# ESP32_Albums.net
KiCad netlist of a schematic drawn in Altium Designer
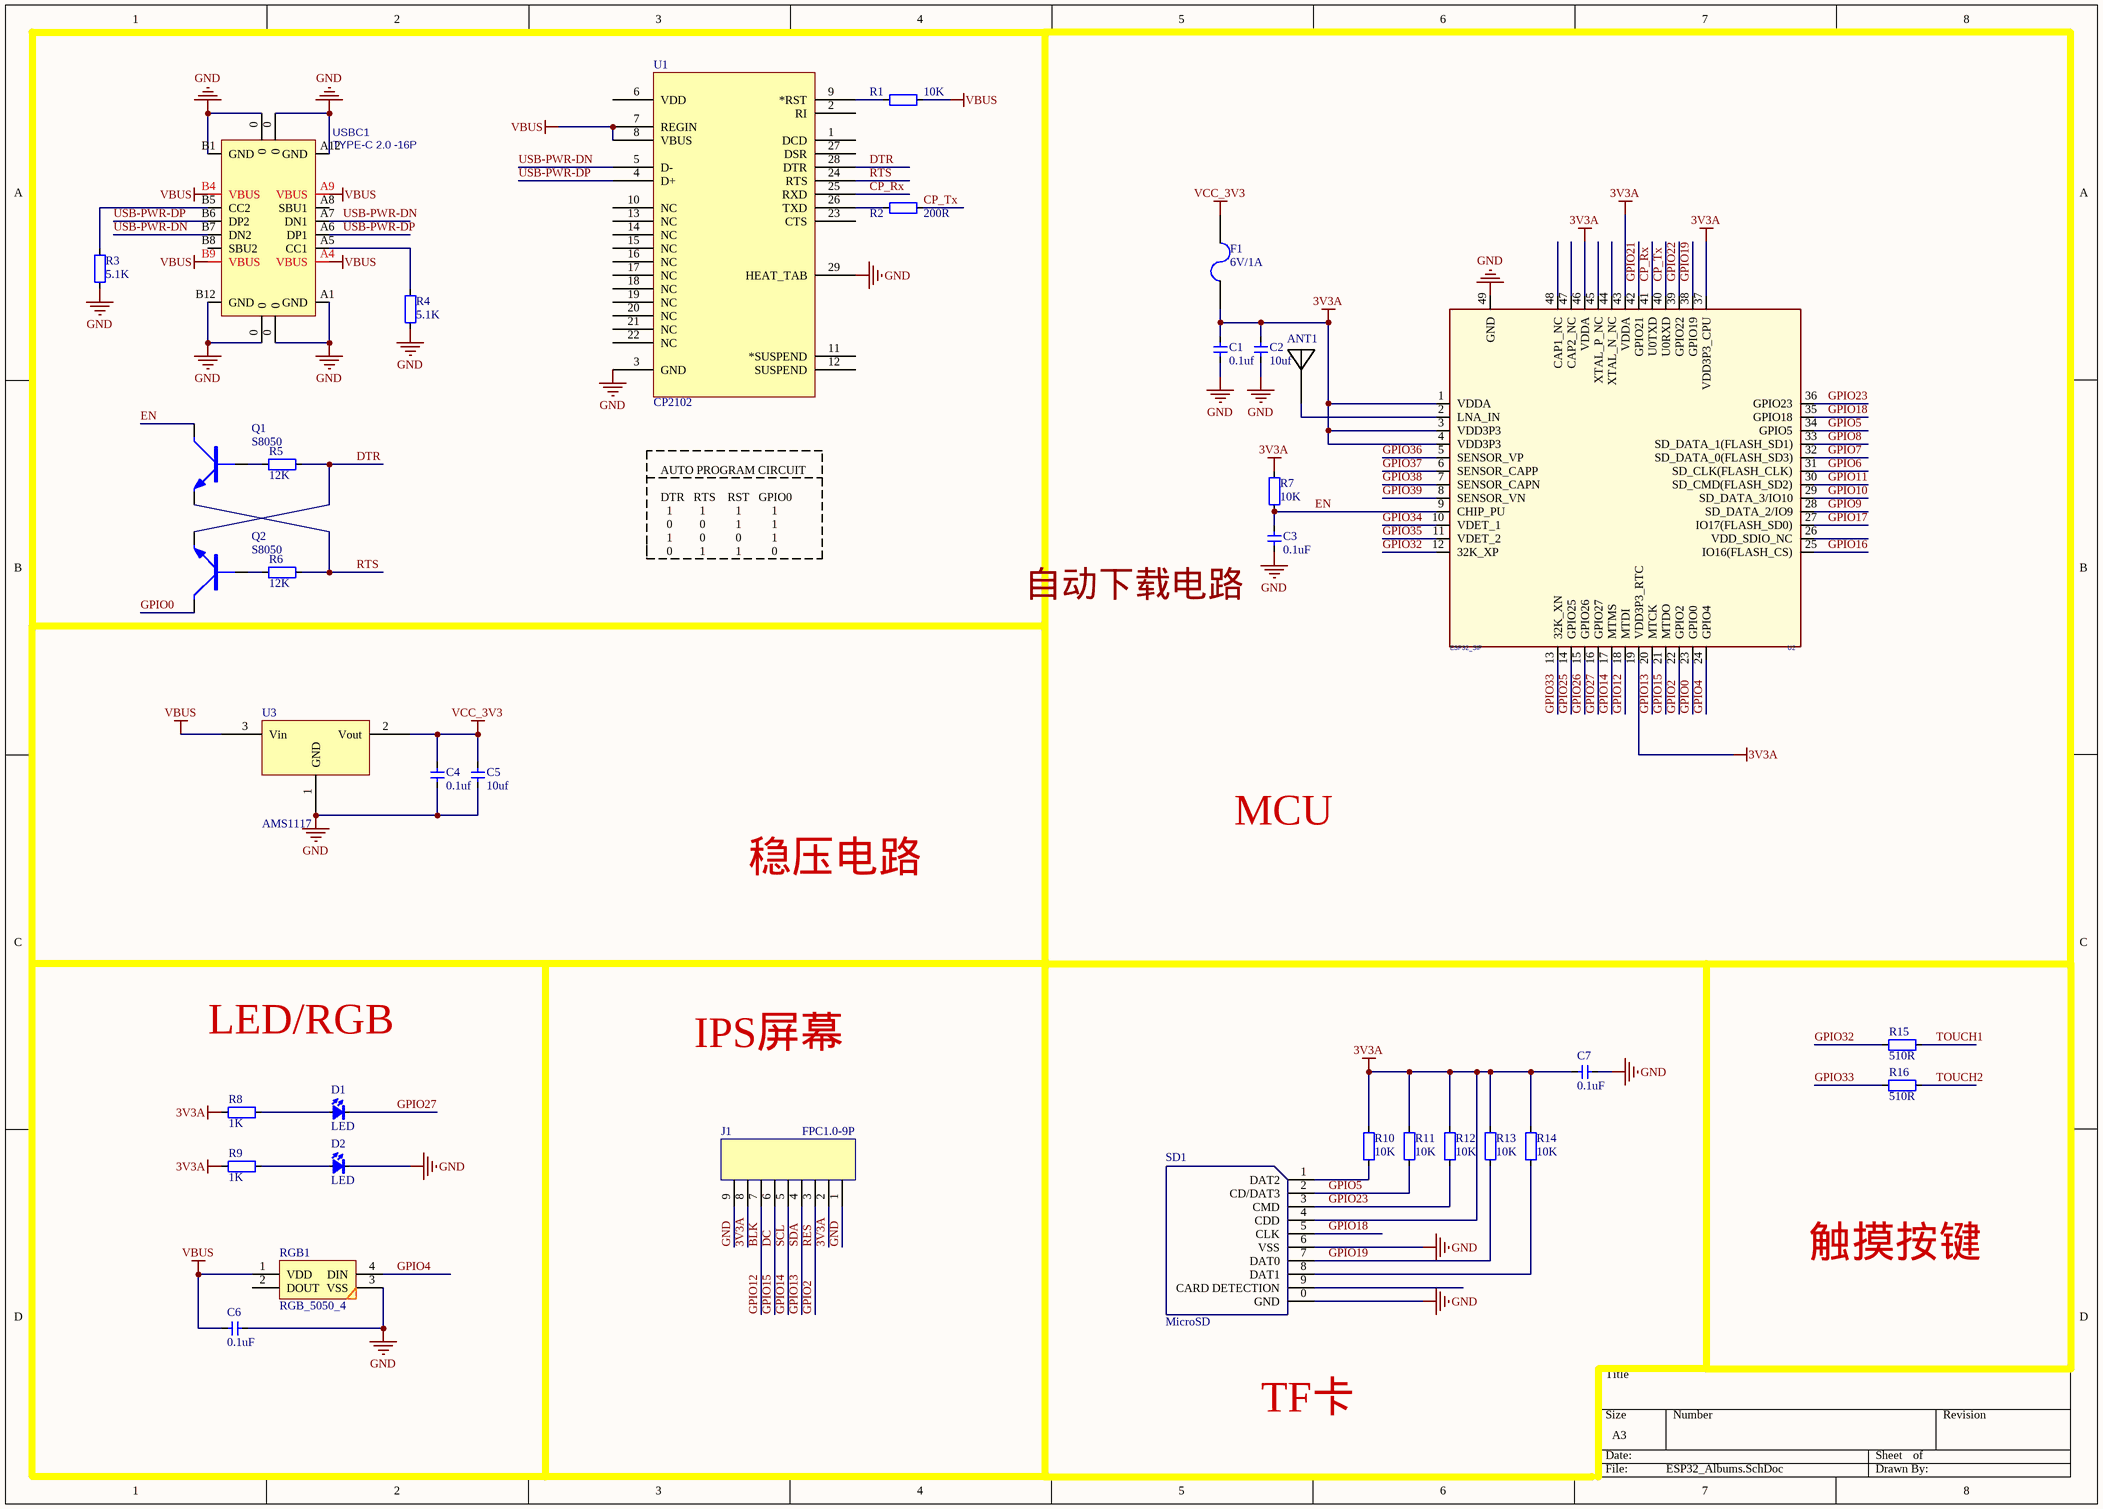
[diagram p0: ESP32_Albums.SchDoc]

(export (version "E")
  (design (tool "Eeschema 10.0.6"))
  (components
    (comp (ref "ANT1")
      (value "ANT2")
      (footprint "ANT2051")
      (description "贴片天线")
      (libsource (lib "射频天线") (part "ANT2"))
    )
    (comp (ref "C1")
      (value "0.1uf")
      (footprint "0603C")
      (description "无极性电容")
      (libsource (lib "电容") (part "CAP"))
    )
    (comp (ref "C2")
      (value "10uf")
      (footprint "0603C")
      (description "无极性电容")
      (libsource (lib "电容") (part "CAP"))
    )
    (comp (ref "C3")
      (value "0.1uF")
      (footprint "0603C")
      (description "无极性电容")
      (libsource (lib "电容") (part "CAP"))
    )
    (comp (ref "C4")
      (value "0.1uf")
      (footprint "0603C")
      (description "无极性电容")
      (libsource (lib "电容") (part "CAP"))
    )
    (comp (ref "C5")
      (value "10uf")
      (footprint "0603C")
      (description "无极性电容")
      (libsource (lib "电容") (part "CAP"))
    )
    (comp (ref "C6")
      (value "0.1uF")
      (footprint "0603C")
      (description "无极性电容")
      (libsource (lib "电容") (part "CAP"))
    )
    (comp (ref "C7")
      (value "0.1uF")
      (footprint "0603C")
      (description "无极性电容")
      (libsource (lib "电容") (part "CAP"))
    )
    (comp (ref "D1") (value "LED") (footprint "LED_0603_R") (libsource (lib "LED") (part "LED")))
    (comp (ref "D2") (value "LED") (footprint "LED_0603_R") (libsource (lib "LED") (part "LED")))
    (comp (ref "F1") (value "6V/1A") (footprint "FUSE-0805") (libsource (lib "保险丝") (part "FUSE")))
    (comp (ref "J1")
      (value "FPC1.0-9P")
      (footprint "FPC1.0-9P")
      (description "贴片")
      (libsource (lib "FPC") (part "FPC1.0-9P"))
    )
    (comp (ref "Q1")
      (value "S8050")
      (footprint "SOT-23")
      (description "NPN三极管")
      (libsource (lib "三极管") (part "NPN"))
    )
    (comp (ref "Q2")
      (value "S8050")
      (footprint "SOT-23")
      (description "NPN三极管")
      (libsource (lib "三极管") (part "NPN"))
    )
    (comp (ref "R1") (value "10K") (footprint "0603R") (libsource (lib "") (part "RES_1")))
    (comp (ref "R2") (value "200R") (footprint "0603R") (libsource (lib "") (part "RES_1")))
    (comp (ref "R3") (value "5.1K") (footprint "0603R") (libsource (lib "电阻") (part "RES")))
    (comp (ref "R4") (value "5.1K") (footprint "0603R") (libsource (lib "电阻") (part "RES")))
    (comp (ref "R5") (value "12K") (footprint "0603R") (libsource (lib "") (part "RES_1")))
    (comp (ref "R6") (value "12K") (footprint "0603R") (libsource (lib "") (part "RES_1")))
    (comp (ref "R7") (value "10K") (footprint "0603R") (libsource (lib "电阻") (part "RES")))
    (comp (ref "R8") (value "1K") (footprint "0603R") (libsource (lib "") (part "RES_1")))
    (comp (ref "R9") (value "1K") (footprint "0603R") (libsource (lib "") (part "RES_1")))
    (comp (ref "R10") (value "10K") (footprint "0603R") (libsource (lib "电阻") (part "RES")))
    (comp (ref "R11") (value "10K") (footprint "0603R") (libsource (lib "电阻") (part "RES")))
    (comp (ref "R12") (value "10K") (footprint "0603R") (libsource (lib "电阻") (part "RES")))
    (comp (ref "R13") (value "10K") (footprint "0603R") (libsource (lib "电阻") (part "RES")))
    (comp (ref "R14") (value "10K") (footprint "0603R") (libsource (lib "电阻") (part "RES")))
    (comp (ref "R15") (value "510R") (footprint "0603R") (libsource (lib "") (part "RES_1")))
    (comp (ref "R16") (value "510R") (footprint "0603R") (libsource (lib "") (part "RES_1")))
    (comp (ref "RGB1")
      (value "RGB_5050_4")
      (footprint "RGB_5050_4")
      (libsource (lib "LED") (part "RGB_5050_4"))
    )
    (comp (ref "SD1") (value "MicroSD") (footprint "Micro SD") (libsource (lib "SD Card") (part "MicroSD")))
    (comp (ref "U1")
      (value "CP2102")
      (footprint "LC-QFN-28_5x5x05P")
      (description "USB转TTL")
      (libsource (lib "通讯系列IC") (part "CP2102"))
    )
    (comp (ref "U2")
      (value "ESP32_SIP")
      (footprint "QFN-48_7X7")
      (libsource (lib "ESP32系列") (part "ESP32-PICO"))
    )
    (comp (ref "U3")
      (value "AMS1117")
      (footprint "SOT223")
      (description "三端稳压芯片")
      (libsource (lib "电源芯片") (part "AMS1117"))
    )
    (comp (ref "USBC1")
      (value "TYPE-C 2.0 -16P")
      (footprint "USB-C-SMD_16P")
      (description "USB2.0 Type-C 16Pin  母座")
      (libsource (lib "USB") (part "USB2.0_Type-C_16Pin"))
    )
  )
  (nets
    (net (code "1") (name "/BLK") (class "Default")
      (node (ref "J1") (pin "7") (pinfunction "7_7") (pintype "passive"))
      (node (ref "U2") (pin "18") (pinfunction "MTDI_18") (pintype "passive"))
    )
    (net (code "2") (name "/CP_Rx") (class "Default")
      (node (ref "U1") (pin "25") (pinfunction "RXD_25") (pintype "passive"))
      (node (ref "U2") (pin "41") (pinfunction "U0TXD_41") (pintype "power_in"))
    )
    (net (code "3") (name "/CP_Tx") (class "Default")
      (node (ref "R2") (pin "2") (pinfunction "2_2") (pintype "passive"))
      (node (ref "U2") (pin "40") (pinfunction "U0RXD_40") (pintype "power_in"))
    )
    (net (code "4") (name "/DC") (class "Default")
      (node (ref "J1") (pin "6") (pinfunction "6_6") (pintype "passive"))
      (node (ref "U2") (pin "21") (pinfunction "MTDO_21") (pintype "passive"))
    )
    (net (code "5") (name "/DTR") (class "Default")
      (node (ref "Q2") (pin "E") (pinfunction "E_E") (pintype "passive"))
      (node (ref "R5") (pin "2") (pinfunction "2_2") (pintype "passive"))
      (node (ref "U1") (pin "28") (pinfunction "DTR_28") (pintype "passive"))
    )
    (net (code "6") (name "/EN") (class "Default")
      (node (ref "C3") (pin "2") (pinfunction "2_2") (pintype "passive"))
      (node (ref "Q1") (pin "C") (pinfunction "C_C") (pintype "passive"))
      (node (ref "R7") (pin "1") (pinfunction "1_1") (pintype "passive"))
      (node (ref "U2") (pin "9") (pinfunction "CHIP_PU_9") (pintype "passive"))
    )
    (net (code "7") (name "/GPIO0") (class "Default")
      (node (ref "Q2") (pin "C") (pinfunction "C_C") (pintype "passive"))
      (node (ref "U2") (pin "23") (pinfunction "GPIO0_23") (pintype "passive"))
    )
    (net (code "8") (name "/GPIO2") (class "Default")
      (node (ref "J1") (pin "3") (pinfunction "3_3") (pintype "passive"))
      (node (ref "U2") (pin "22") (pinfunction "GPIO2_22") (pintype "passive"))
    )
    (net (code "9") (name "/GPIO4") (class "Default")
      (node (ref "RGB1") (pin "4") (pinfunction "DIN_4") (pintype "passive"))
      (node (ref "U2") (pin "24") (pinfunction "GPIO4_24") (pintype "passive"))
    )
    (net (code "10") (name "/GPIO5") (class "Default")
      (node (ref "R11") (pin "1") (pinfunction "1_1") (pintype "passive"))
      (node (ref "SD1") (pin "2") (pinfunction "CD/DAT3_2") (pintype "passive"))
      (node (ref "U2") (pin "34") (pinfunction "GPIO5_34") (pintype "passive"))
    )
    (net (code "11") (name "/GPIO6") (class "Default")
      (node (ref "U2") (pin "31") (pinfunction "SD_CLK(FLASH_CLK)_31") (pintype "passive"))
    )
    (net (code "12") (name "/GPIO7") (class "Default")
      (node (ref "U2") (pin "32") (pinfunction "SD_DATA_0(FLASH_SD3)_32") (pintype "passive"))
    )
    (net (code "13") (name "/GPIO8") (class "Default")
      (node (ref "U2") (pin "33") (pinfunction "SD_DATA_1(FLASH_SD1)_33") (pintype "passive"))
    )
    (net (code "14") (name "/GPIO9") (class "Default")
      (node (ref "U2") (pin "28") (pinfunction "SD_DATA_2/IO9_28") (pintype "passive"))
    )
    (net (code "15") (name "/GPIO10") (class "Default")
      (node (ref "U2") (pin "29") (pinfunction "SD_DATA_3/IO10_29") (pintype "passive"))
    )
    (net (code "16") (name "/GPIO11") (class "Default")
      (node (ref "U2") (pin "30") (pinfunction "SD_CMD(FLASH_SD2)_30") (pintype "passive"))
    )
    (net (code "17") (name "/GPIO13") (class "Default")
      (node (ref "J1") (pin "4") (pinfunction "4_4") (pintype "passive"))
      (node (ref "U2") (pin "20") (pinfunction "MTCK_20") (pintype "passive"))
    )
    (net (code "18") (name "/GPIO14") (class "Default")
      (node (ref "J1") (pin "5") (pinfunction "5_5") (pintype "passive"))
      (node (ref "U2") (pin "17") (pinfunction "MTMS_17") (pintype "passive"))
    )
    (net (code "19") (name "/GPIO16") (class "Default")
      (node (ref "U2") (pin "25") (pinfunction "IO16(FLASH_CS)_25") (pintype "passive"))
    )
    (net (code "20") (name "/GPIO17") (class "Default")
      (node (ref "U2") (pin "27") (pinfunction "IO17(FLASH_SD0)_27") (pintype "passive"))
    )
    (net (code "21") (name "/GPIO18") (class "Default")
      (node (ref "SD1") (pin "5") (pinfunction "CLK_5") (pintype "passive"))
      (node (ref "U2") (pin "35") (pinfunction "GPIO18_35") (pintype "passive"))
    )
    (net (code "22") (name "/GPIO19") (class "Default")
      (node (ref "R13") (pin "1") (pinfunction "1_1") (pintype "passive"))
      (node (ref "SD1") (pin "7") (pinfunction "DAT0_7") (pintype "passive"))
      (node (ref "U2") (pin "38") (pinfunction "GPIO19_38") (pintype "passive"))
    )
    (net (code "23") (name "/GPIO21") (class "Default")
      (node (ref "U2") (pin "42") (pinfunction "GPIO21_42") (pintype "passive"))
    )
    (net (code "24") (name "/GPIO22") (class "Default")
      (node (ref "U2") (pin "39") (pinfunction "GPIO22_39") (pintype "passive"))
    )
    (net (code "25") (name "/GPIO23") (class "Default")
      (node (ref "R12") (pin "1") (pinfunction "1_1") (pintype "passive"))
      (node (ref "SD1") (pin "3") (pinfunction "CMD_3") (pintype "passive"))
      (node (ref "U2") (pin "36") (pinfunction "GPIO23_36") (pintype "passive"))
    )
    (net (code "26") (name "/GPIO25") (class "Default")
      (node (ref "U2") (pin "14") (pinfunction "GPIO25_14") (pintype "passive"))
    )
    (net (code "27") (name "/GPIO26") (class "Default")
      (node (ref "U2") (pin "15") (pinfunction "GPIO26_15") (pintype "passive"))
    )
    (net (code "28") (name "/GPIO27") (class "Default")
      (node (ref "D1") (pin "1") (pinfunction "A_1") (pintype "passive"))
      (node (ref "U2") (pin "16") (pinfunction "GPIO27_16") (pintype "passive"))
    )
    (net (code "29") (name "/GPIO32") (class "Default")
      (node (ref "R15") (pin "1") (pinfunction "1_1") (pintype "passive"))
      (node (ref "U2") (pin "12") (pinfunction "32K_XP_12") (pintype "passive"))
    )
    (net (code "30") (name "/GPIO33") (class "Default")
      (node (ref "R16") (pin "1") (pinfunction "1_1") (pintype "passive"))
      (node (ref "U2") (pin "13") (pinfunction "32K_XN_13") (pintype "passive"))
    )
    (net (code "31") (name "/GPIO34") (class "Default")
      (node (ref "U2") (pin "10") (pinfunction "VDET_1_10") (pintype "passive"))
    )
    (net (code "32") (name "/GPIO35") (class "Default")
      (node (ref "U2") (pin "11") (pinfunction "VDET_2_11") (pintype "passive"))
    )
    (net (code "33") (name "/GPIO36") (class "Default")
      (node (ref "U2") (pin "5") (pinfunction "SENSOR_VP_5") (pintype "passive"))
    )
    (net (code "34") (name "/GPIO37") (class "Default")
      (node (ref "U2") (pin "6") (pinfunction "SENSOR_CAPP_6") (pintype "passive"))
    )
    (net (code "35") (name "/GPIO38") (class "Default")
      (node (ref "U2") (pin "7") (pinfunction "SENSOR_CAPN_7") (pintype "passive"))
    )
    (net (code "36") (name "/GPIO39") (class "Default")
      (node (ref "U2") (pin "8") (pinfunction "SENSOR_VN_8") (pintype "passive"))
    )
    (net (code "37") (name "/RTS") (class "Default")
      (node (ref "Q1") (pin "E") (pinfunction "E_E") (pintype "passive"))
      (node (ref "R6") (pin "2") (pinfunction "2_2") (pintype "passive"))
      (node (ref "U1") (pin "24") (pinfunction "RTS_24") (pintype "passive"))
    )
    (net (code "38") (name "/TOUCH1") (class "Default")
      (node (ref "R15") (pin "2") (pinfunction "2_2") (pintype "passive"))
    )
    (net (code "39") (name "/TOUCH2") (class "Default")
      (node (ref "R16") (pin "2") (pinfunction "2_2") (pintype "passive"))
    )
    (net (code "40") (name "/USB-PWR-DN") (class "Default")
      (node (ref "U1") (pin "5") (pinfunction "D-_5") (pintype "passive"))
      (node (ref "USBC1") (pin "A7") (pinfunction "DN1_A7") (pintype "passive"))
      (node (ref "USBC1") (pin "B7") (pinfunction "DN2_B7") (pintype "passive"))
    )
    (net (code "41") (name "/USB-PWR-DP") (class "Default")
      (node (ref "U1") (pin "4") (pinfunction "D+_4") (pintype "passive"))
      (node (ref "USBC1") (pin "A6") (pinfunction "DP1_A6") (pintype "passive"))
      (node (ref "USBC1") (pin "B6") (pinfunction "DP2_B6") (pintype "passive"))
    )
    (net (code "42") (name "3V3A") (class "Default")
      (node (ref "C1") (pin "2") (pinfunction "2_2") (pintype "passive"))
      (node (ref "C2") (pin "2") (pinfunction "2_2") (pintype "passive"))
      (node (ref "C7") (pin "1") (pinfunction "1_1") (pintype "passive"))
      (node (ref "F1") (pin "1") (pinfunction "1_1") (pintype "passive"))
      (node (ref "J1") (pin "2") (pinfunction "2_2") (pintype "passive"))
      (node (ref "J1") (pin "8") (pinfunction "8_8") (pintype "passive"))
      (node (ref "R10") (pin "2") (pinfunction "2_2") (pintype "passive"))
      (node (ref "R11") (pin "2") (pinfunction "2_2") (pintype "passive"))
      (node (ref "R12") (pin "2") (pinfunction "2_2") (pintype "passive"))
      (node (ref "R13") (pin "2") (pinfunction "2_2") (pintype "passive"))
      (node (ref "R14") (pin "2") (pinfunction "2_2") (pintype "passive"))
      (node (ref "R7") (pin "2") (pinfunction "2_2") (pintype "passive"))
      (node (ref "R8") (pin "1") (pinfunction "1_1") (pintype "passive"))
      (node (ref "R9") (pin "1") (pinfunction "1_1") (pintype "passive"))
      (node (ref "SD1") (pin "4") (pinfunction "CDD_4") (pintype "passive"))
      (node (ref "U2") (pin "1") (pinfunction "VDDA_1") (pintype "power_in"))
      (node (ref "U2") (pin "19") (pinfunction "VDD3P3_RTC_19") (pintype "power_in"))
      (node (ref "U2") (pin "3") (pinfunction "VDD3P3_3") (pintype "power_in"))
      (node (ref "U2") (pin "37") (pinfunction "VDD3P3_CPU_37") (pintype "power_in"))
      (node (ref "U2") (pin "4") (pinfunction "VDD3P3_4") (pintype "power_in"))
      (node (ref "U2") (pin "43") (pinfunction "VDDA_43") (pintype "power_in"))
      (node (ref "U2") (pin "46") (pinfunction "VDDA_46") (pintype "power_in"))
    )
    (net (code "43") (name "GND") (class "Default")
      (node (ref "C1") (pin "1") (pinfunction "1_1") (pintype "passive"))
      (node (ref "C2") (pin "1") (pinfunction "1_1") (pintype "passive"))
      (node (ref "C3") (pin "1") (pinfunction "1_1") (pintype "passive"))
      (node (ref "C4") (pin "1") (pinfunction "1_1") (pintype "passive"))
      (node (ref "C5") (pin "1") (pinfunction "1_1") (pintype "passive"))
      (node (ref "C6") (pin "2") (pinfunction "2_2") (pintype "passive"))
      (node (ref "C7") (pin "2") (pinfunction "2_2") (pintype "passive"))
      (node (ref "D2") (pin "1") (pinfunction "A_1") (pintype "passive"))
      (node (ref "J1") (pin "1") (pinfunction "1_1") (pintype "passive"))
      (node (ref "J1") (pin "9") (pinfunction "9_9") (pintype "passive"))
      (node (ref "R3") (pin "1") (pinfunction "1_1") (pintype "passive"))
      (node (ref "R4") (pin "1") (pinfunction "1_1") (pintype "passive"))
      (node (ref "RGB1") (pin "3") (pinfunction "VSS_3") (pintype "passive"))
      (node (ref "SD1") (pin "0") (pinfunction "GND_0") (pintype "passive"))
      (node (ref "SD1") (pin "6") (pinfunction "VSS_6") (pintype "passive"))
      (node (ref "U1") (pin "29") (pinfunction "HEAT_TAB_29") (pintype "passive"))
      (node (ref "U1") (pin "3") (pinfunction "GND_3") (pintype "passive"))
      (node (ref "U2") (pin "49") (pinfunction "GND_49") (pintype "power_in"))
      (node (ref "U3") (pin "1") (pinfunction "GND_1") (pintype "passive"))
      (node (ref "USBC1") (pin "0") (pinfunction "0_0") (pintype "passive"))
      (node (ref "USBC1") (pin "A1") (pinfunction "GND_A1") (pintype "passive"))
      (node (ref "USBC1") (pin "A12") (pinfunction "GND_A12") (pintype "passive"))
      (node (ref "USBC1") (pin "B1") (pinfunction "GND_B1") (pintype "passive"))
      (node (ref "USBC1") (pin "B12") (pinfunction "GND_B12") (pintype "passive"))
    )
    (net (code "44") (name "Net-(D1-K)") (class "Default")
      (node (ref "D1") (pin "2") (pinfunction "K_2") (pintype "passive"))
      (node (ref "R8") (pin "2") (pinfunction "2_2") (pintype "passive"))
    )
    (net (code "45") (name "Net-(D2-K)") (class "Default")
      (node (ref "D2") (pin "2") (pinfunction "K_2") (pintype "passive"))
      (node (ref "R9") (pin "2") (pinfunction "2_2") (pintype "passive"))
    )
    (net (code "46") (name "Net-(Q1-PadB)") (class "Default")
      (node (ref "Q1") (pin "B") (pinfunction "B_B") (pintype "passive"))
      (node (ref "R5") (pin "1") (pinfunction "1_1") (pintype "passive"))
    )
    (net (code "47") (name "Net-(Q2-PadB)") (class "Default")
      (node (ref "Q2") (pin "B") (pinfunction "B_B") (pintype "passive"))
      (node (ref "R6") (pin "1") (pinfunction "1_1") (pintype "passive"))
    )
    (net (code "48") (name "Net-(SD1-DAT1)") (class "Default")
      (node (ref "R14") (pin "1") (pinfunction "1_1") (pintype "passive"))
      (node (ref "SD1") (pin "8") (pinfunction "DAT1_8") (pintype "passive"))
    )
    (net (code "49") (name "Net-(SD1-DAT2)") (class "Default")
      (node (ref "R10") (pin "1") (pinfunction "1_1") (pintype "passive"))
      (node (ref "SD1") (pin "1") (pinfunction "DAT2_1") (pintype "passive"))
    )
    (net (code "50") (name "Net-(U1-*RST)") (class "Default")
      (node (ref "R1") (pin "1") (pinfunction "1_1") (pintype "passive"))
      (node (ref "U1") (pin "9") (pinfunction "*RST_9") (pintype "passive"))
    )
    (net (code "51") (name "Net-(U1-TXD)") (class "Default")
      (node (ref "R2") (pin "1") (pinfunction "1_1") (pintype "passive"))
      (node (ref "U1") (pin "26") (pinfunction "TXD_26") (pintype "passive"))
    )
    (net (code "52") (name "Net-(U2-LNA_IN)") (class "Default")
      (node (ref "ANT1") (pin "1") (pinfunction "1_1") (pintype "passive"))
      (node (ref "U2") (pin "2") (pinfunction "LNA_IN_2") (pintype "passive"))
    )
    (net (code "53") (name "Net-(USBC1-CC1)") (class "Default")
      (node (ref "R4") (pin "2") (pinfunction "2_2") (pintype "passive"))
      (node (ref "USBC1") (pin "A5") (pinfunction "CC1_A5") (pintype "passive"))
    )
    (net (code "54") (name "Net-(USBC1-CC2)") (class "Default")
      (node (ref "R3") (pin "2") (pinfunction "2_2") (pintype "passive"))
      (node (ref "USBC1") (pin "B5") (pinfunction "CC2_B5") (pintype "passive"))
    )
    (net (code "55") (name "VBUS") (class "Default")
      (node (ref "C6") (pin "1") (pinfunction "1_1") (pintype "passive"))
      (node (ref "R1") (pin "2") (pinfunction "2_2") (pintype "passive"))
      (node (ref "RGB1") (pin "1") (pinfunction "VDD_1") (pintype "passive"))
      (node (ref "U1") (pin "7") (pinfunction "REGIN_7") (pintype "passive"))
      (node (ref "U1") (pin "8") (pinfunction "VBUS_8") (pintype "passive"))
      (node (ref "U3") (pin "3") (pinfunction "Vin_3") (pintype "passive"))
      (node (ref "USBC1") (pin "A4") (pinfunction "VBUS_A4") (pintype "passive"))
      (node (ref "USBC1") (pin "A9") (pinfunction "VBUS_A9") (pintype "passive"))
      (node (ref "USBC1") (pin "B4") (pinfunction "VBUS_B4") (pintype "passive"))
      (node (ref "USBC1") (pin "B9") (pinfunction "VBUS_B9") (pintype "passive"))
    )
    (net (code "56") (name "VCC_3V3") (class "Default")
      (node (ref "C4") (pin "2") (pinfunction "2_2") (pintype "passive"))
      (node (ref "C5") (pin "2") (pinfunction "2_2") (pintype "passive"))
      (node (ref "F1") (pin "2") (pinfunction "2_2") (pintype "passive"))
      (node (ref "U3") (pin "2") (pinfunction "Vout_2") (pintype "passive"))
    )
    (net (code "57") (name "unconnected-(RGB1-DOUT-Pad2)") (class "Default")
      (node (ref "RGB1") (pin "2") (pinfunction "DOUT_2") (pintype "passive"))
    )
    (net (code "58") (name "unconnected-(SD1-CARD_DETECTION-Pad9)") (class "Default")
      (node (ref "SD1") (pin "9") (pinfunction "CARD_DETECTION_9") (pintype "passive"))
    )
    (net (code "59") (name "unconnected-(U1-*SUSPEND-Pad11)") (class "Default")
      (node (ref "U1") (pin "11") (pinfunction "*SUSPEND_11") (pintype "passive"))
    )
    (net (code "60") (name "unconnected-(U1-CTS-Pad23)") (class "Default")
      (node (ref "U1") (pin "23") (pinfunction "CTS_23") (pintype "passive"))
    )
    (net (code "61") (name "unconnected-(U1-DCD-Pad1)") (class "Default")
      (node (ref "U1") (pin "1") (pinfunction "DCD_1") (pintype "passive"))
    )
    (net (code "62") (name "unconnected-(U1-DSR-Pad27)") (class "Default")
      (node (ref "U1") (pin "27") (pinfunction "DSR_27") (pintype "passive"))
    )
    (net (code "63") (name "unconnected-(U1-NC-Pad10)") (class "Default")
      (node (ref "U1") (pin "10") (pinfunction "NC_10") (pintype "passive"))
    )
    (net (code "64") (name "unconnected-(U1-NC-Pad13)") (class "Default")
      (node (ref "U1") (pin "13") (pinfunction "NC_13") (pintype "passive"))
    )
    (net (code "65") (name "unconnected-(U1-NC-Pad14)") (class "Default")
      (node (ref "U1") (pin "14") (pinfunction "NC_14") (pintype "passive"))
    )
    (net (code "66") (name "unconnected-(U1-NC-Pad15)") (class "Default")
      (node (ref "U1") (pin "15") (pinfunction "NC_15") (pintype "passive"))
    )
    (net (code "67") (name "unconnected-(U1-NC-Pad16)") (class "Default")
      (node (ref "U1") (pin "16") (pinfunction "NC_16") (pintype "passive"))
    )
    (net (code "68") (name "unconnected-(U1-NC-Pad17)") (class "Default")
      (node (ref "U1") (pin "17") (pinfunction "NC_17") (pintype "passive"))
    )
    (net (code "69") (name "unconnected-(U1-NC-Pad18)") (class "Default")
      (node (ref "U1") (pin "18") (pinfunction "NC_18") (pintype "passive"))
    )
    (net (code "70") (name "unconnected-(U1-NC-Pad19)") (class "Default")
      (node (ref "U1") (pin "19") (pinfunction "NC_19") (pintype "passive"))
    )
    (net (code "71") (name "unconnected-(U1-NC-Pad20)") (class "Default")
      (node (ref "U1") (pin "20") (pinfunction "NC_20") (pintype "passive"))
    )
    (net (code "72") (name "unconnected-(U1-NC-Pad21)") (class "Default")
      (node (ref "U1") (pin "21") (pinfunction "NC_21") (pintype "passive"))
    )
    (net (code "73") (name "unconnected-(U1-NC-Pad22)") (class "Default")
      (node (ref "U1") (pin "22") (pinfunction "NC_22") (pintype "passive"))
    )
    (net (code "74") (name "unconnected-(U1-RI-Pad2)") (class "Default")
      (node (ref "U1") (pin "2") (pinfunction "RI_2") (pintype "passive"))
    )
    (net (code "75") (name "unconnected-(U1-SUSPEND-Pad12)") (class "Default")
      (node (ref "U1") (pin "12") (pinfunction "SUSPEND_12") (pintype "passive"))
    )
    (net (code "76") (name "unconnected-(U1-VDD-Pad6)") (class "Default")
      (node (ref "U1") (pin "6") (pinfunction "VDD_6") (pintype "passive"))
    )
    (net (code "77") (name "unconnected-(U2-CAP1_NC-Pad48)") (class "Default")
      (node (ref "U2") (pin "48") (pinfunction "CAP1_NC_48") (pintype "passive"))
    )
    (net (code "78") (name "unconnected-(U2-CAP2_NC-Pad47)") (class "Default")
      (node (ref "U2") (pin "47") (pinfunction "CAP2_NC_47") (pintype "passive"))
    )
    (net (code "79") (name "unconnected-(U2-VDD_SDIO_NC-Pad26)") (class "Default")
      (node (ref "U2") (pin "26") (pinfunction "VDD_SDIO_NC_26") (pintype "passive"))
    )
    (net (code "80") (name "unconnected-(U2-XTAL_N_NC-Pad44)") (class "Default")
      (node (ref "U2") (pin "44") (pinfunction "XTAL_N_NC_44") (pintype "passive"))
    )
    (net (code "81") (name "unconnected-(U2-XTAL_P_NC-Pad45)") (class "Default")
      (node (ref "U2") (pin "45") (pinfunction "XTAL_P_NC_45") (pintype "passive"))
    )
    (net (code "82") (name "unconnected-(USBC1-SBU1-PadA8)") (class "Default")
      (node (ref "USBC1") (pin "A8") (pinfunction "SBU1_A8") (pintype "passive"))
    )
    (net (code "83") (name "unconnected-(USBC1-SBU2-PadB8)") (class "Default")
      (node (ref "USBC1") (pin "B8") (pinfunction "SBU2_B8") (pintype "passive"))
    )
  )
)
